# PCB-SPKTRLIGHT.net
KiCad netlist of a schematic drawn in EAGLE
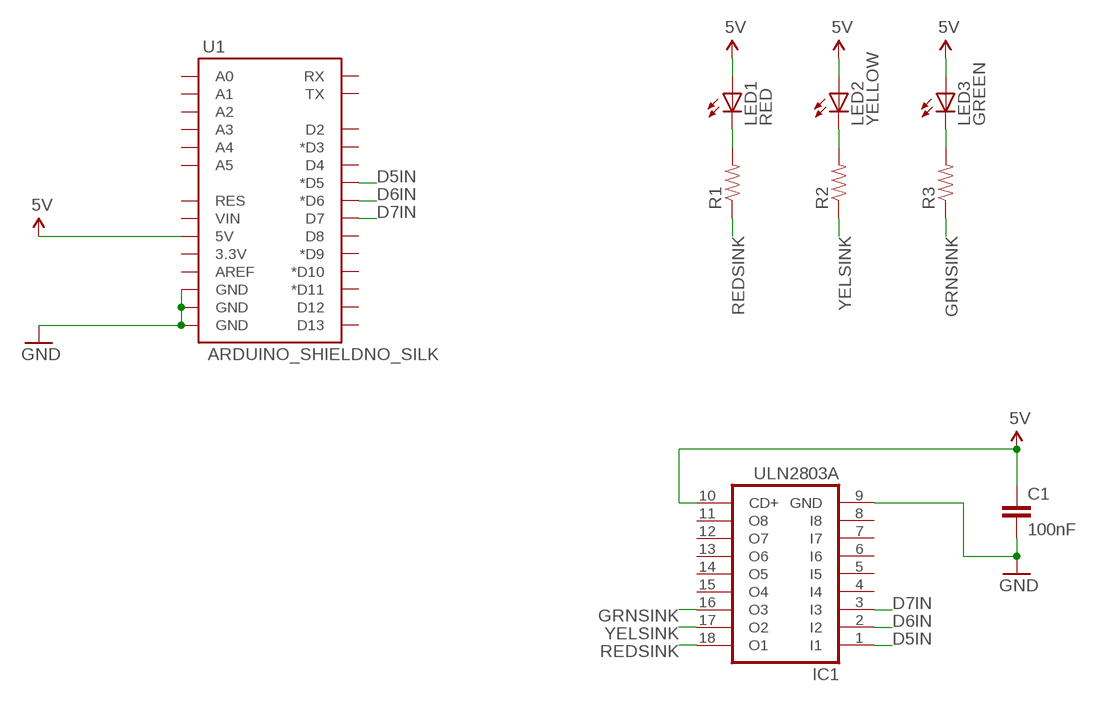
[diagram p0: schematic, sheet 1]

(export (version "E")
  (design (tool "Eeschema 10.0.6"))
  (components
    (comp (ref "C1")
      (value "100nF")
      (footprint "eagle-import:0805")
      (libsource (lib "eagle-import") (part "CAP0805"))
    )
    (comp (ref "IC1")
      (value "ULN2803A")
      (footprint "eagle-import:SO18W")
      (libsource (lib "eagle-import") (part "ULN2803ASO18W"))
    )
    (comp (ref "LED1")
      (value "RED")
      (footprint "eagle-import:LED5MM")
      (libsource (lib "eagle-import") (part "LED5MM"))
    )
    (comp (ref "LED2")
      (value "YELLOW")
      (footprint "eagle-import:LED5MM")
      (libsource (lib "eagle-import") (part "LED5MM"))
    )
    (comp (ref "LED3")
      (value "GREEN")
      (footprint "eagle-import:LED5MM")
      (libsource (lib "eagle-import") (part "LED5MM"))
    )
    (comp (ref "R1")
      (value "RESISTORPTH-1/4W")
      (footprint "eagle-import:AXIAL-0.4")
      (libsource (lib "eagle-import") (part "RESISTORPTH-1/4W"))
    )
    (comp (ref "R2")
      (value "RESISTORPTH-1/4W")
      (footprint "eagle-import:AXIAL-0.4")
      (libsource (lib "eagle-import") (part "RESISTORPTH-1/4W"))
    )
    (comp (ref "R3")
      (value "RESISTORPTH-1/4W")
      (footprint "eagle-import:AXIAL-0.4")
      (libsource (lib "eagle-import") (part "RESISTORPTH-1/4W"))
    )
    (comp (ref "U1")
      (value "ARDUINO_SHIELDNO_SILK")
      (footprint "eagle-import:DUEMILANOVE_VIAS")
      (libsource (lib "eagle-import") (part "ARDUINO_SHIELDNO_SILK"))
    )
  )
  (nets
    (net (code "1") (name "/D5IN") (class "Default")
      (node (ref "IC1") (pin "1") (pinfunction "I1_1") (pintype "input"))
      (node (ref "U1") (pin "D5") (pinfunction "*D5_D5") (pintype "bidirectional"))
    )
    (net (code "2") (name "/D6IN") (class "Default")
      (node (ref "IC1") (pin "2") (pinfunction "I2_2") (pintype "input"))
      (node (ref "U1") (pin "D6") (pinfunction "*D6_D6") (pintype "bidirectional"))
    )
    (net (code "3") (name "/D7IN") (class "Default")
      (node (ref "IC1") (pin "3") (pinfunction "I3_3") (pintype "input"))
      (node (ref "U1") (pin "D7") (pinfunction "D7_D7") (pintype "bidirectional"))
    )
    (net (code "4") (name "/GRNSINK") (class "Default")
      (node (ref "IC1") (pin "16") (pinfunction "O3_16") (pintype "open_collector"))
      (node (ref "R3") (pin "P$1") (pinfunction "1_P$1") (pintype "passive"))
    )
    (net (code "5") (name "/REDSINK") (class "Default")
      (node (ref "IC1") (pin "18") (pinfunction "O1_18") (pintype "open_collector"))
      (node (ref "R1") (pin "P$1") (pinfunction "1_P$1") (pintype "passive"))
    )
    (net (code "6") (name "/YELSINK") (class "Default")
      (node (ref "IC1") (pin "17") (pinfunction "O2_17") (pintype "open_collector"))
      (node (ref "R2") (pin "P$1") (pinfunction "1_P$1") (pintype "passive"))
    )
    (net (code "7") (name "5V") (class "Default")
      (node (ref "C1") (pin "1") (pinfunction "1_1") (pintype "passive"))
      (node (ref "IC1") (pin "10") (pinfunction "CD+_10") (pintype "passive"))
      (node (ref "LED1") (pin "A") (pinfunction "A_A") (pintype "passive"))
      (node (ref "LED2") (pin "A") (pinfunction "A_A") (pintype "passive"))
      (node (ref "LED3") (pin "A") (pinfunction "A_A") (pintype "passive"))
      (node (ref "U1") (pin "5V") (pinfunction "5V_5V") (pintype "bidirectional"))
    )
    (net (code "8") (name "GND") (class "Default")
      (node (ref "C1") (pin "2") (pinfunction "2_2") (pintype "passive"))
      (node (ref "IC1") (pin "9") (pinfunction "GND_9") (pintype "power_in"))
      (node (ref "U1") (pin "GND@0") (pinfunction "GND_GND@0") (pintype "bidirectional"))
      (node (ref "U1") (pin "GND@1") (pinfunction "GND_GND@1") (pintype "bidirectional"))
      (node (ref "U1") (pin "GND@2") (pinfunction "GND_GND@2") (pintype "bidirectional"))
    )
    (net (code "9") (name "Net-(LED1-C)") (class "Default")
      (node (ref "LED1") (pin "K") (pinfunction "C_K") (pintype "passive"))
      (node (ref "R1") (pin "P$2") (pinfunction "2_P$2") (pintype "passive"))
    )
    (net (code "10") (name "Net-(LED2-C)") (class "Default")
      (node (ref "LED2") (pin "K") (pinfunction "C_K") (pintype "passive"))
      (node (ref "R2") (pin "P$2") (pinfunction "2_P$2") (pintype "passive"))
    )
    (net (code "11") (name "Net-(LED3-C)") (class "Default")
      (node (ref "LED3") (pin "K") (pinfunction "C_K") (pintype "passive"))
      (node (ref "R3") (pin "P$2") (pinfunction "2_P$2") (pintype "passive"))
    )
    (net (code "12") (name "unconnected-(IC1-I4-Pad4)") (class "Default")
      (node (ref "IC1") (pin "4") (pinfunction "I4_4") (pintype "input"))
    )
    (net (code "13") (name "unconnected-(IC1-I5-Pad5)") (class "Default")
      (node (ref "IC1") (pin "5") (pinfunction "I5_5") (pintype "input"))
    )
    (net (code "14") (name "unconnected-(IC1-I6-Pad6)") (class "Default")
      (node (ref "IC1") (pin "6") (pinfunction "I6_6") (pintype "input"))
    )
    (net (code "15") (name "unconnected-(IC1-I7-Pad7)") (class "Default")
      (node (ref "IC1") (pin "7") (pinfunction "I7_7") (pintype "input"))
    )
    (net (code "16") (name "unconnected-(IC1-I8-Pad8)") (class "Default")
      (node (ref "IC1") (pin "8") (pinfunction "I8_8") (pintype "input"))
    )
    (net (code "17") (name "unconnected-(IC1-O4-Pad15)") (class "Default")
      (node (ref "IC1") (pin "15") (pinfunction "O4_15") (pintype "open_collector"))
    )
    (net (code "18") (name "unconnected-(IC1-O5-Pad14)") (class "Default")
      (node (ref "IC1") (pin "14") (pinfunction "O5_14") (pintype "open_collector"))
    )
    (net (code "19") (name "unconnected-(IC1-O6-Pad13)") (class "Default")
      (node (ref "IC1") (pin "13") (pinfunction "O6_13") (pintype "open_collector"))
    )
    (net (code "20") (name "unconnected-(IC1-O7-Pad12)") (class "Default")
      (node (ref "IC1") (pin "12") (pinfunction "O7_12") (pintype "open_collector"))
    )
    (net (code "21") (name "unconnected-(IC1-O8-Pad11)") (class "Default")
      (node (ref "IC1") (pin "11") (pinfunction "O8_11") (pintype "open_collector"))
    )
    (net (code "22") (name "unconnected-(U1-*D3-PadD3)") (class "Default")
      (node (ref "U1") (pin "D3") (pinfunction "*D3_D3") (pintype "bidirectional"))
    )
    (net (code "23") (name "unconnected-(U1-*D9-PadD9)") (class "Default")
      (node (ref "U1") (pin "D9") (pinfunction "*D9_D9") (pintype "bidirectional"))
    )
    (net (code "24") (name "unconnected-(U1-*D10-PadD10)") (class "Default")
      (node (ref "U1") (pin "D10") (pinfunction "*D10_D10") (pintype "bidirectional"))
    )
    (net (code "25") (name "unconnected-(U1-*D11-PadD11)") (class "Default")
      (node (ref "U1") (pin "D11") (pinfunction "*D11_D11") (pintype "bidirectional"))
    )
    (net (code "26") (name "unconnected-(U1-Pad3.3V)") (class "Default")
      (node (ref "U1") (pin "3.3V") (pinfunction "3.3V_3.3V") (pintype "bidirectional"))
    )
    (net (code "27") (name "unconnected-(U1-PadA0)") (class "Default")
      (node (ref "U1") (pin "A0") (pinfunction "A0_A0") (pintype "bidirectional"))
    )
    (net (code "28") (name "unconnected-(U1-PadA1)") (class "Default")
      (node (ref "U1") (pin "A1") (pinfunction "A1_A1") (pintype "bidirectional"))
    )
    (net (code "29") (name "unconnected-(U1-PadA2)") (class "Default")
      (node (ref "U1") (pin "A2") (pinfunction "A2_A2") (pintype "bidirectional"))
    )
    (net (code "30") (name "unconnected-(U1-PadA3)") (class "Default")
      (node (ref "U1") (pin "A3") (pinfunction "A3_A3") (pintype "bidirectional"))
    )
    (net (code "31") (name "unconnected-(U1-PadA4)") (class "Default")
      (node (ref "U1") (pin "A4") (pinfunction "A4_A4") (pintype "bidirectional"))
    )
    (net (code "32") (name "unconnected-(U1-PadA5)") (class "Default")
      (node (ref "U1") (pin "A5") (pinfunction "A5_A5") (pintype "bidirectional"))
    )
    (net (code "33") (name "unconnected-(U1-PadAREF)") (class "Default")
      (node (ref "U1") (pin "AREF") (pinfunction "AREF_AREF") (pintype "bidirectional"))
    )
    (net (code "34") (name "unconnected-(U1-PadD2)") (class "Default")
      (node (ref "U1") (pin "D2") (pinfunction "D2_D2") (pintype "bidirectional"))
    )
    (net (code "35") (name "unconnected-(U1-PadD4)") (class "Default")
      (node (ref "U1") (pin "D4") (pinfunction "D4_D4") (pintype "bidirectional"))
    )
    (net (code "36") (name "unconnected-(U1-PadD8)") (class "Default")
      (node (ref "U1") (pin "D8") (pinfunction "D8_D8") (pintype "bidirectional"))
    )
    (net (code "37") (name "unconnected-(U1-PadD12)") (class "Default")
      (node (ref "U1") (pin "D12") (pinfunction "D12_D12") (pintype "bidirectional"))
    )
    (net (code "38") (name "unconnected-(U1-PadD13)") (class "Default")
      (node (ref "U1") (pin "D13") (pinfunction "D13_D13") (pintype "bidirectional"))
    )
    (net (code "39") (name "unconnected-(U1-PadRES)") (class "Default")
      (node (ref "U1") (pin "RES") (pinfunction "RES_RES") (pintype "bidirectional"))
    )
    (net (code "40") (name "unconnected-(U1-PadRX)") (class "Default")
      (node (ref "U1") (pin "RX") (pinfunction "RX_RX") (pintype "bidirectional"))
    )
    (net (code "41") (name "unconnected-(U1-PadTX)") (class "Default")
      (node (ref "U1") (pin "TX") (pinfunction "TX_TX") (pintype "bidirectional"))
    )
    (net (code "42") (name "unconnected-(U1-PadVIN)") (class "Default")
      (node (ref "U1") (pin "VIN") (pinfunction "VIN_VIN") (pintype "bidirectional"))
    )
  )
)
